# SW_12.net
KiCad netlist of a schematic drawn in Altium Designer
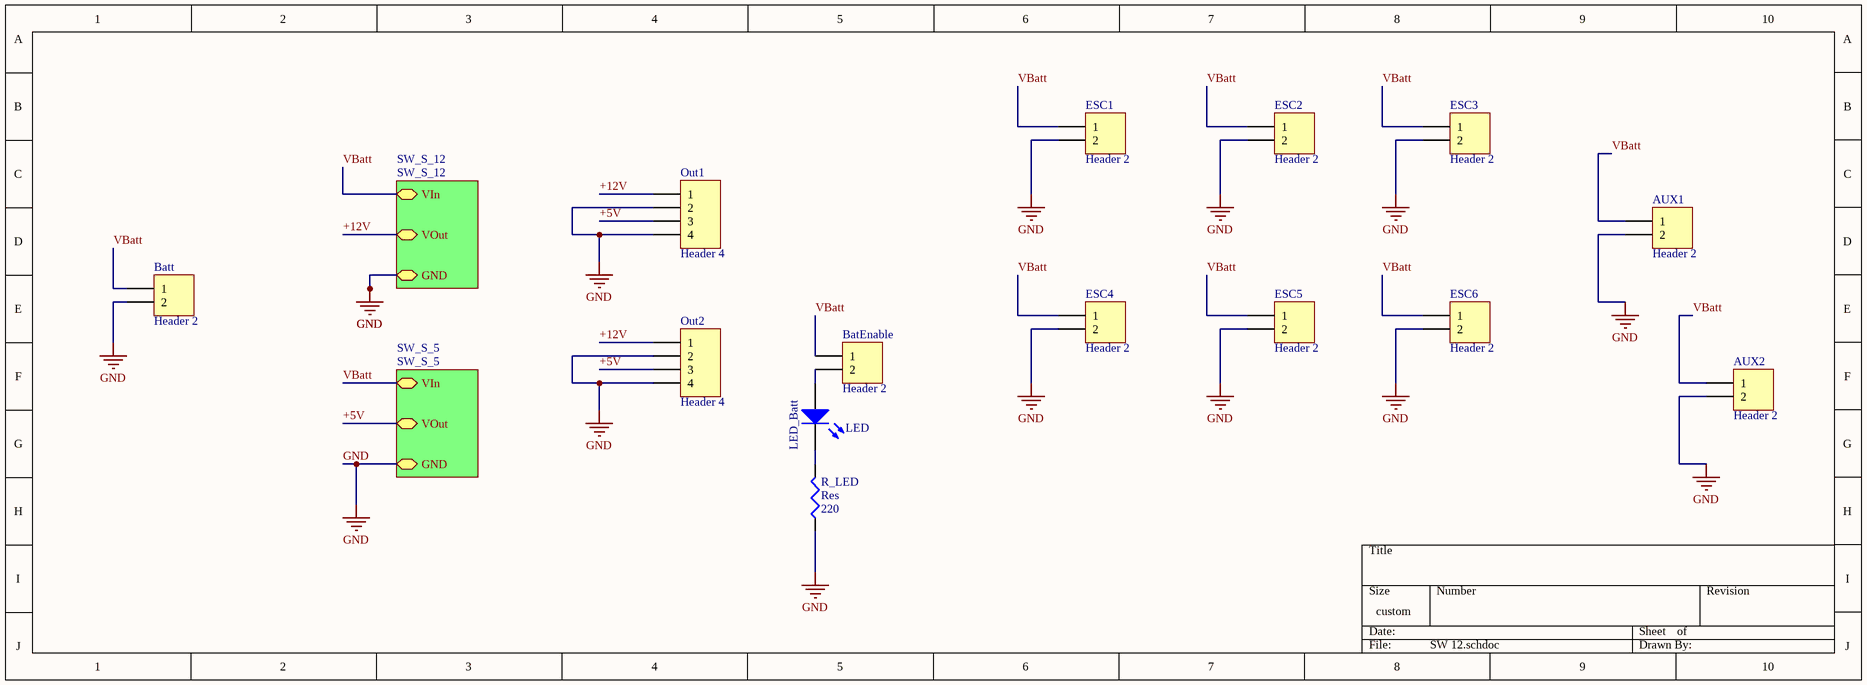
[diagram p0: SW 12.schdoc]

(export (version "E")
  (design (tool "Eeschema 10.0.6"))
  (components
    (comp (ref "AUX1")
      (value "Header 2")
      (footprint "14 AWG Power Footprint")
      (description "Header, 2-Pin")
      (fields (field (name "PUBLISHER") "Altium Limited"))
      (libsource (lib "Miscellaneous Connectors") (part "Header 2"))
    )
    (comp (ref "AUX2")
      (value "Header 2")
      (footprint "14 AWG Power Footprint")
      (description "Header, 2-Pin")
      (fields (field (name "PUBLISHER") "Altium Limited"))
      (libsource (lib "Miscellaneous Connectors") (part "Header 2"))
    )
    (comp (ref "BatEnable")
      (value "Header 2")
      (footprint "HDR1X2")
      (description "Header, 2-Pin")
      (fields (field (name "PUBLISHER") "Altium Limited"))
      (libsource (lib "Miscellaneous Connectors") (part "Header 2"))
    )
    (comp (ref "Batt")
      (value "Header 2")
      (footprint "10 AWG Power Footprint")
      (description "Header, 2-Pin")
      (fields (field (name "PUBLISHER") "Altium Limited"))
      (libsource (lib "Miscellaneous Connectors") (part "Header 2"))
    )
    (comp (ref "ESC1")
      (value "Header 2")
      (footprint "14 AWG Power Footprint")
      (description "Header, 2-Pin")
      (fields (field (name "PUBLISHER") "Altium Limited"))
      (libsource (lib "Miscellaneous Connectors") (part "Header 2"))
    )
    (comp (ref "ESC2")
      (value "Header 2")
      (footprint "14 AWG Power Footprint")
      (description "Header, 2-Pin")
      (fields (field (name "PUBLISHER") "Altium Limited"))
      (libsource (lib "Miscellaneous Connectors") (part "Header 2"))
    )
    (comp (ref "ESC3")
      (value "Header 2")
      (footprint "14 AWG Power Footprint")
      (description "Header, 2-Pin")
      (fields (field (name "PUBLISHER") "Altium Limited"))
      (libsource (lib "Miscellaneous Connectors") (part "Header 2"))
    )
    (comp (ref "ESC4")
      (value "Header 2")
      (footprint "14 AWG Power Footprint")
      (description "Header, 2-Pin")
      (fields (field (name "PUBLISHER") "Altium Limited"))
      (libsource (lib "Miscellaneous Connectors") (part "Header 2"))
    )
    (comp (ref "ESC5")
      (value "Header 2")
      (footprint "14 AWG Power Footprint")
      (description "Header, 2-Pin")
      (fields (field (name "PUBLISHER") "Altium Limited"))
      (libsource (lib "Miscellaneous Connectors") (part "Header 2"))
    )
    (comp (ref "ESC6")
      (value "Header 2")
      (footprint "14 AWG Power Footprint")
      (description "Header, 2-Pin")
      (fields (field (name "PUBLISHER") "Altium Limited"))
      (libsource (lib "Miscellaneous Connectors") (part "Header 2"))
    )
    (comp (ref "LED_Batt")
      (value "LED")
      (footprint "6-0805_L")
      (description "Typical RED, GREEN, YELLOW, AMBER GaAs LED")
      (fields (field (name "PUBLISHER") "Altium Limited"))
      (libsource (lib "Miscellaneous Devices") (part "LED2"))
    )
    (comp (ref "Out1")
      (value "Header 4")
      (footprint "HDR1X4")
      (description "Header, 4-Pin")
      (fields (field (name "PUBLISHER") "Altium Limited"))
      (libsource (lib "Miscellaneous Connectors") (part "Header 4"))
    )
    (comp (ref "Out2")
      (value "Header 4")
      (footprint "HDR1X4")
      (description "Header, 4-Pin")
      (fields (field (name "PUBLISHER") "Altium Limited"))
      (libsource (lib "Miscellaneous Connectors") (part "Header 4"))
    )
    (comp (ref "R_LED")
      (value "Res")
      (footprint "6-0805_L")
      (description "Resistor")
      (fields (field (name "ALTIUM_VALUE") "220") (field (name "PUBLISHER") "Altium Limited"))
      (libsource (lib "Miscellaneous Devices") (part "Res3"))
    )
  )
  (nets
    (net (code "1") (name "/+5V") (class "Default")
      (node (ref "Out1") (pin "3") (pinfunction "3_3") (pintype "passive"))
      (node (ref "Out2") (pin "3") (pinfunction "3_3") (pintype "passive"))
    )
    (net (code "2") (name "/+12V") (class "Default")
      (node (ref "Out1") (pin "1") (pinfunction "1_1") (pintype "passive"))
      (node (ref "Out2") (pin "1") (pinfunction "1_1") (pintype "passive"))
    )
    (net (code "3") (name "/VBatt") (class "Default")
      (node (ref "AUX1") (pin "1") (pinfunction "1_1") (pintype "passive"))
      (node (ref "AUX2") (pin "1") (pinfunction "1_1") (pintype "passive"))
      (node (ref "BatEnable") (pin "1") (pinfunction "1_1") (pintype "passive"))
      (node (ref "Batt") (pin "1") (pinfunction "1_1") (pintype "passive"))
      (node (ref "ESC1") (pin "1") (pinfunction "1_1") (pintype "passive"))
      (node (ref "ESC2") (pin "1") (pinfunction "1_1") (pintype "passive"))
      (node (ref "ESC3") (pin "1") (pinfunction "1_1") (pintype "passive"))
      (node (ref "ESC4") (pin "1") (pinfunction "1_1") (pintype "passive"))
      (node (ref "ESC5") (pin "1") (pinfunction "1_1") (pintype "passive"))
      (node (ref "ESC6") (pin "1") (pinfunction "1_1") (pintype "passive"))
    )
    (net (code "4") (name "GND") (class "Default")
      (node (ref "AUX1") (pin "2") (pinfunction "2_2") (pintype "passive"))
      (node (ref "AUX2") (pin "2") (pinfunction "2_2") (pintype "passive"))
      (node (ref "Batt") (pin "2") (pinfunction "2_2") (pintype "passive"))
      (node (ref "ESC1") (pin "2") (pinfunction "2_2") (pintype "passive"))
      (node (ref "ESC2") (pin "2") (pinfunction "2_2") (pintype "passive"))
      (node (ref "ESC3") (pin "2") (pinfunction "2_2") (pintype "passive"))
      (node (ref "ESC4") (pin "2") (pinfunction "2_2") (pintype "passive"))
      (node (ref "ESC5") (pin "2") (pinfunction "2_2") (pintype "passive"))
      (node (ref "ESC6") (pin "2") (pinfunction "2_2") (pintype "passive"))
      (node (ref "Out1") (pin "2") (pinfunction "2_2") (pintype "passive"))
      (node (ref "Out1") (pin "4") (pinfunction "4_4") (pintype "passive"))
      (node (ref "Out2") (pin "2") (pinfunction "2_2") (pintype "passive"))
      (node (ref "Out2") (pin "4") (pinfunction "4_4") (pintype "passive"))
      (node (ref "R_LED") (pin "1") (pinfunction "1_1") (pintype "passive"))
    )
    (net (code "5") (name "Net-(LED_Batt-A)") (class "Default")
      (node (ref "BatEnable") (pin "2") (pinfunction "2_2") (pintype "passive"))
      (node (ref "LED_Batt") (pin "1") (pinfunction "A_1") (pintype "passive"))
    )
    (net (code "6") (name "Net-(LED_Batt-K)") (class "Default")
      (node (ref "LED_Batt") (pin "2") (pinfunction "K_2") (pintype "passive"))
      (node (ref "R_LED") (pin "2") (pinfunction "2_2") (pintype "passive"))
    )
  )
)
